# micro.net
KiCad netlist of a schematic drawn in Altium Designer
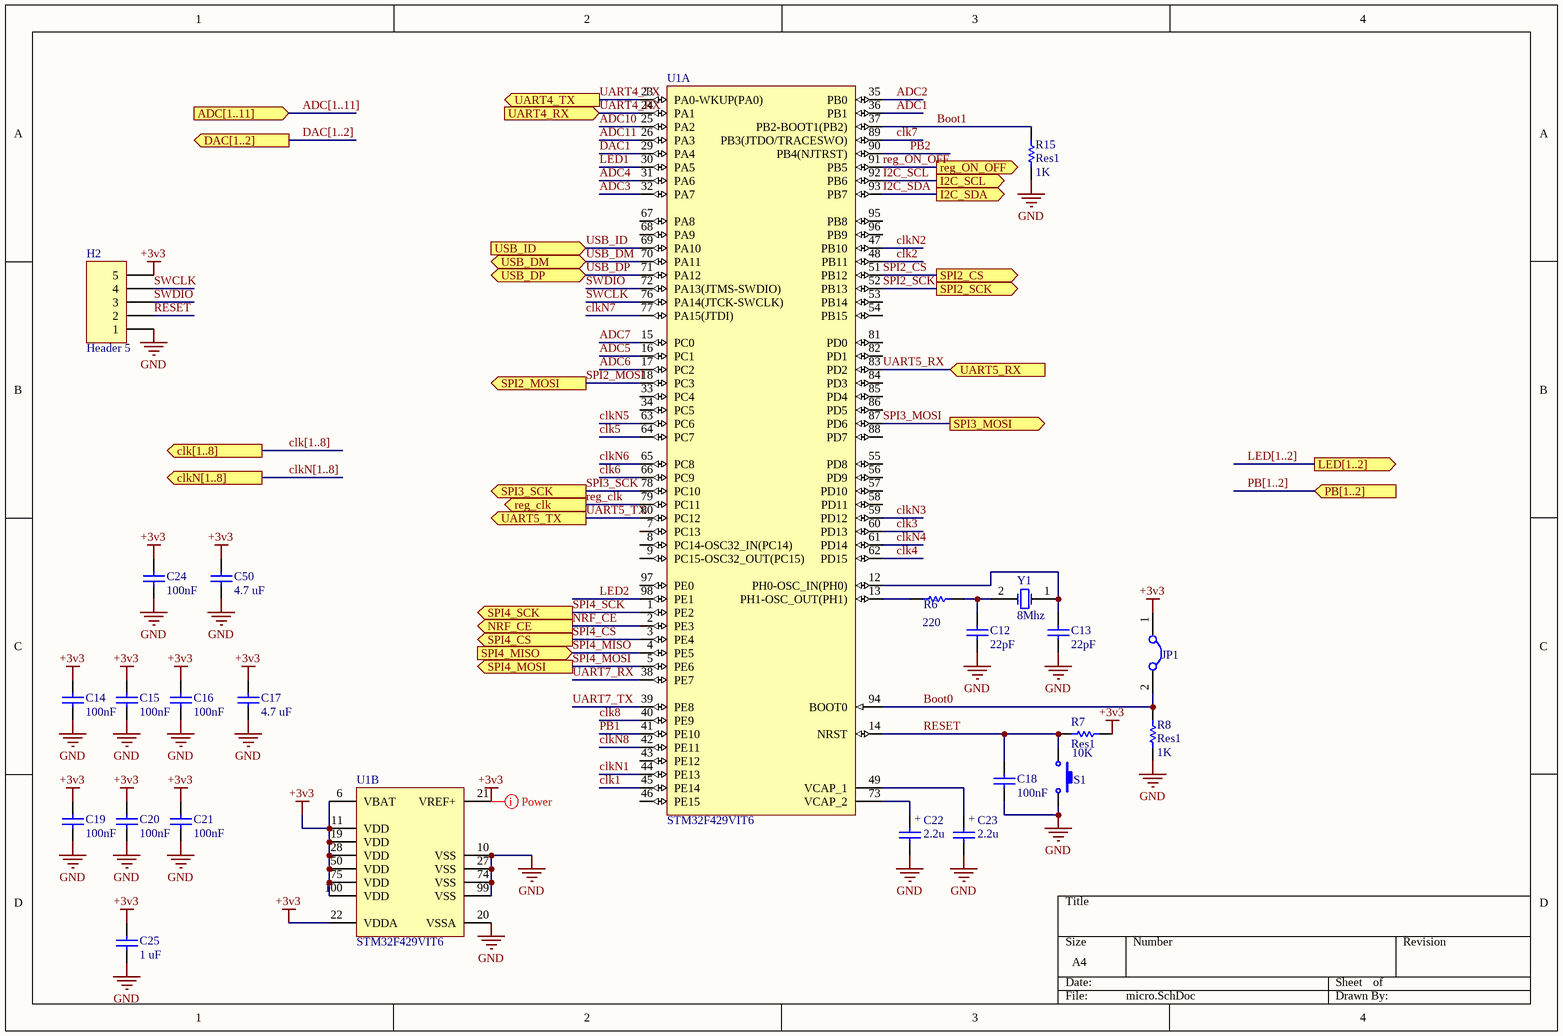
[diagram p0: micro.SchDoc]

(export (version "E")
  (design (tool "Eeschema 10.0.6"))
  (components
    (comp (ref "C12")
      (value "22pF")
      (footprint "SMD_CAP_0805")
      (description "Capacitor")
      (fields (field (name "Comment") "Cap") (field (name "PUBLISHER") "Altium Limited"))
      (libsource (lib "Miscellaneous Devices") (part "Cap"))
    )
    (comp (ref "C13")
      (value "22pF")
      (footprint "SMD_CAP_0805")
      (description "Capacitor")
      (fields (field (name "Comment") "Cap") (field (name "PUBLISHER") "Altium Limited"))
      (libsource (lib "Miscellaneous Devices") (part "Cap"))
    )
    (comp (ref "C14")
      (value "100nF")
      (footprint "SMD_CAP_0805")
      (description "Capacitor")
      (fields (field (name "PUBLISHER") "Altium Limited"))
      (libsource (lib "Miscellaneous Devices") (part "Cap"))
    )
    (comp (ref "C15")
      (value "100nF")
      (footprint "SMD_CAP_0805")
      (description "Capacitor")
      (fields (field (name "PUBLISHER") "Altium Limited"))
      (libsource (lib "Miscellaneous Devices") (part "Cap"))
    )
    (comp (ref "C16")
      (value "100nF")
      (footprint "SMD_CAP_0805")
      (description "Capacitor")
      (fields (field (name "PUBLISHER") "Altium Limited"))
      (libsource (lib "Miscellaneous Devices") (part "Cap"))
    )
    (comp (ref "C17")
      (value "4.7 uF")
      (footprint "SMD_CAP_0805")
      (fields (field (name "Comment") "Cap"))
      (libsource (lib "common0") (part "Cap"))
    )
    (comp (ref "C18")
      (value "100nF")
      (footprint "SMD_CAP_0805")
      (description "Capacitor")
      (fields (field (name "Comment") "Cap") (field (name "PUBLISHER") "Altium Limited"))
      (libsource (lib "Miscellaneous Devices") (part "Cap"))
    )
    (comp (ref "C19")
      (value "100nF")
      (footprint "SMD_CAP_0805")
      (description "Capacitor")
      (fields (field (name "PUBLISHER") "Altium Limited"))
      (libsource (lib "Miscellaneous Devices") (part "Cap"))
    )
    (comp (ref "C20")
      (value "100nF")
      (footprint "SMD_CAP_0805")
      (description "Capacitor")
      (fields (field (name "PUBLISHER") "Altium Limited"))
      (libsource (lib "Miscellaneous Devices") (part "Cap"))
    )
    (comp (ref "C21")
      (value "100nF")
      (footprint "SMD_CAP_0805")
      (description "Capacitor")
      (fields (field (name "PUBLISHER") "Altium Limited"))
      (libsource (lib "Miscellaneous Devices") (part "Cap"))
    )
    (comp (ref "C22")
      (value "2.2u")
      (footprint "CAPP 1206 (3216X18L) Size A")
      (description "tantal size a")
      (libsource (lib "Altium library (www.AVRelec.com)") (part "Cap Pol"))
    )
    (comp (ref "C23")
      (value "2.2u")
      (footprint "CAPP 1206 (3216X18L) Size A")
      (description "tantal size a")
      (libsource (lib "Altium library (www.AVRelec.com)") (part "Cap Pol"))
    )
    (comp (ref "C24")
      (value "100nF")
      (footprint "SMD_CAP_0805")
      (description "Capacitor")
      (fields (field (name "PUBLISHER") "Altium Limited"))
      (libsource (lib "Miscellaneous Devices") (part "Cap"))
    )
    (comp (ref "C25")
      (value "1 uF")
      (footprint "CAPP 1206 (3216X18L) Size A")
      (fields (field (name "Comment") "Cap"))
      (libsource (lib "common0") (part "Cap"))
    )
    (comp (ref "C50")
      (value "4.7 uF")
      (footprint "SMD_CAP_0805")
      (fields (field (name "Comment") "Cap"))
      (libsource (lib "common0") (part "Cap"))
    )
    (comp (ref "H2")
      (value "Header 5")
      (footprint "HDR1X5")
      (description "Header, 5-Pin")
      (fields (field (name "PUBLISHER") "Altium Limited"))
      (libsource (lib "Miscellaneous Connectors") (part "Header 5"))
    )
    (comp (ref "JP1")
      (value "Jumper")
      (footprint "Jumper Small - 2.54 - GRAY")
      (libsource (lib "Altium (2)") (part "Jumper"))
    )
    (comp (ref "R6")
      (value "220")
      (footprint "RES 0805 (2012X06L)")
      (description "Resistor")
      (fields (field (name "Comment") "Res1") (field (name "PUBLISHER") "Altium Limited"))
      (libsource (lib "Miscellaneous Devices") (part "Res1"))
    )
    (comp (ref "R7")
      (value "Res1")
      (footprint "RES 0805 (2012X06L)")
      (description "Resistor")
      (fields (field (name "ALTIUM_VALUE") "10K") (field (name "PUBLISHER") "Altium Limited"))
      (libsource (lib "Miscellaneous Devices") (part "Res1"))
    )
    (comp (ref "R8")
      (value "Res1")
      (footprint "RES 0805 (2012X06L)")
      (description "Resistor")
      (fields (field (name "ALTIUM_VALUE") "1K") (field (name "PUBLISHER") "Altium Limited"))
      (libsource (lib "Miscellaneous Devices") (part "Res1"))
    )
    (comp (ref "R15")
      (value "Res1")
      (footprint "RES 0805 (2012X06L)")
      (description "Resistor")
      (fields (field (name "ALTIUM_VALUE") "1K") (field (name "PUBLISHER") "Altium Limited"))
      (libsource (lib "Miscellaneous Devices") (part "Res1"))
    )
    (comp (ref "S1")
      (value "Switch PB")
      (footprint "Switch - Push to On")
      (description "Push Button Switch")
      (libsource (lib "Altium (2)") (part "Switch PB"))
    )
    (comp (ref "U1")
      (value "STM32F429VIT6")
      (footprint "STM-LQFP100_M")
      (fields (field (name "MANUFACTURER") "STMicroelectronics"))
      (libsource (lib "STMicroelectronics STM32 F4") (part "STM32F429VIT6"))
    )
    (comp (ref "Y1")
      (value "8Mhz")
      (footprint "CRYSTAL Small")
      (description "Crystal Oscillator")
      (fields (field (name "PUBLISHER") "Altium Limited"))
      (libsource (lib "Miscellaneous Devices") (part "XTAL"))
    )
  )
  (nets
    (net (code "4") (name "+3v3") (class "Default")
      (node (ref "C14") (pin "2") (pinfunction "2_2") (pintype "passive"))
      (node (ref "C15") (pin "2") (pinfunction "2_2") (pintype "passive"))
      (node (ref "C16") (pin "2") (pinfunction "2_2") (pintype "passive"))
      (node (ref "C17") (pin "1") (pinfunction "1_1") (pintype "passive"))
      (node (ref "C19") (pin "2") (pinfunction "2_2") (pintype "passive"))
      (node (ref "C20") (pin "2") (pinfunction "2_2") (pintype "passive"))
      (node (ref "C21") (pin "2") (pinfunction "2_2") (pintype "passive"))
      (node (ref "C24") (pin "2") (pinfunction "2_2") (pintype "passive"))
      (node (ref "C25") (pin "1") (pinfunction "1_1") (pintype "passive"))
      (node (ref "C50") (pin "1") (pinfunction "1_1") (pintype "passive"))
      (node (ref "H2") (pin "5") (pinfunction "5_5") (pintype "passive"))
      (node (ref "JP1") (pin "1") (pinfunction "1_1") (pintype "passive"))
      (node (ref "R7") (pin "1") (pinfunction "1_1") (pintype "passive"))
      (node (ref "U1") (pin "100") (pinfunction "VDD_100") (pintype "power_in"))
      (node (ref "U1") (pin "11") (pinfunction "VDD_11") (pintype "power_in"))
      (node (ref "U1") (pin "19") (pinfunction "VDD_19") (pintype "power_in"))
      (node (ref "U1") (pin "21") (pinfunction "VREF+_21") (pintype "power_in"))
      (node (ref "U1") (pin "22") (pinfunction "VDDA_22") (pintype "power_in"))
      (node (ref "U1") (pin "28") (pinfunction "VDD_28") (pintype "power_in"))
      (node (ref "U1") (pin "50") (pinfunction "VDD_50") (pintype "power_in"))
      (node (ref "U1") (pin "6") (pinfunction "VBAT_6") (pintype "power_in"))
      (node (ref "U1") (pin "75") (pinfunction "VDD_75") (pintype "power_in"))
    )
    (net (code "5") (name "/ADC1") (class "Default")
      (node (ref "U1") (pin "36") (pinfunction "PB1_36") (pintype "bidirectional"))
    )
    (net (code "6") (name "/ADC2") (class "Default")
      (node (ref "U1") (pin "35") (pinfunction "PB0_35") (pintype "bidirectional"))
    )
    (net (code "7") (name "/ADC3") (class "Default")
      (node (ref "U1") (pin "32") (pinfunction "PA7_32") (pintype "bidirectional"))
    )
    (net (code "8") (name "/ADC4") (class "Default")
      (node (ref "U1") (pin "31") (pinfunction "PA6_31") (pintype "bidirectional"))
    )
    (net (code "9") (name "/ADC5") (class "Default")
      (node (ref "U1") (pin "16") (pinfunction "PC1_16") (pintype "bidirectional"))
    )
    (net (code "10") (name "/ADC6") (class "Default")
      (node (ref "U1") (pin "17") (pinfunction "PC2_17") (pintype "bidirectional"))
    )
    (net (code "11") (name "/ADC7") (class "Default")
      (node (ref "U1") (pin "15") (pinfunction "PC0_15") (pintype "bidirectional"))
    )
    (net (code "12") (name "/ADC10") (class "Default")
      (node (ref "U1") (pin "25") (pinfunction "PA2_25") (pintype "bidirectional"))
    )
    (net (code "13") (name "/ADC11") (class "Default")
      (node (ref "U1") (pin "26") (pinfunction "PA3_26") (pintype "bidirectional"))
    )
    (net (code "15") (name "/Boot0") (class "Default")
      (node (ref "JP1") (pin "2") (pinfunction "2_2") (pintype "passive"))
      (node (ref "R8") (pin "2") (pinfunction "2_2") (pintype "passive"))
      (node (ref "U1") (pin "94") (pinfunction "BOOT0_94") (pintype "input"))
    )
    (net (code "16") (name "/Boot1") (class "Default")
      (node (ref "R15") (pin "2") (pinfunction "2_2") (pintype "passive"))
      (node (ref "U1") (pin "37") (pinfunction "PB2-BOOT1(PB2)_37") (pintype "bidirectional"))
    )
    (net (code "17") (name "/DAC1") (class "Default")
      (node (ref "U1") (pin "29") (pinfunction "PA4_29") (pintype "bidirectional"))
    )
    (net (code "19") (name "/I2C_SCL") (class "Default")
      (node (ref "U1") (pin "92") (pinfunction "PB6_92") (pintype "bidirectional"))
    )
    (net (code "20") (name "/I2C_SDA") (class "Default")
      (node (ref "U1") (pin "93") (pinfunction "PB7_93") (pintype "bidirectional"))
    )
    (net (code "21") (name "/LED1") (class "Default")
      (node (ref "U1") (pin "30") (pinfunction "PA5_30") (pintype "bidirectional"))
    )
    (net (code "22") (name "/LED2") (class "Default")
      (node (ref "U1") (pin "98") (pinfunction "PE1_98") (pintype "bidirectional"))
    )
    (net (code "24") (name "/NRF_CE") (class "Default")
      (node (ref "U1") (pin "2") (pinfunction "PE3_2") (pintype "bidirectional"))
    )
    (net (code "25") (name "/PB1") (class "Default")
      (node (ref "U1") (pin "41") (pinfunction "PE10_41") (pintype "bidirectional"))
    )
    (net (code "26") (name "/PB2") (class "Default")
      (node (ref "U1") (pin "90") (pinfunction "PB4(NJTRST)_90") (pintype "bidirectional"))
    )
    (net (code "28") (name "/RESET") (class "Default")
      (node (ref "C18") (pin "2") (pinfunction "2_2") (pintype "passive"))
      (node (ref "H2") (pin "2") (pinfunction "2_2") (pintype "passive"))
      (node (ref "R7") (pin "2") (pinfunction "2_2") (pintype "passive"))
      (node (ref "S1") (pin "1") (pinfunction "1_1") (pintype "passive"))
      (node (ref "U1") (pin "14") (pinfunction "NRST_14") (pintype "bidirectional"))
    )
    (net (code "29") (name "/SPI2_CS") (class "Default")
      (node (ref "U1") (pin "51") (pinfunction "PB12_51") (pintype "bidirectional"))
    )
    (net (code "30") (name "/SPI2_MOSI") (class "Default")
      (node (ref "U1") (pin "18") (pinfunction "PC3_18") (pintype "bidirectional"))
    )
    (net (code "31") (name "/SPI2_SCK") (class "Default")
      (node (ref "U1") (pin "52") (pinfunction "PB13_52") (pintype "bidirectional"))
    )
    (net (code "32") (name "/SPI3_MOSI") (class "Default")
      (node (ref "U1") (pin "87") (pinfunction "PD6_87") (pintype "bidirectional"))
    )
    (net (code "33") (name "/SPI3_SCK") (class "Default")
      (node (ref "U1") (pin "78") (pinfunction "PC10_78") (pintype "bidirectional"))
    )
    (net (code "34") (name "/SPI4_CS") (class "Default")
      (node (ref "U1") (pin "3") (pinfunction "PE4_3") (pintype "bidirectional"))
    )
    (net (code "35") (name "/SPI4_MISO") (class "Default")
      (node (ref "U1") (pin "4") (pinfunction "PE5_4") (pintype "bidirectional"))
    )
    (net (code "36") (name "/SPI4_MOSI") (class "Default")
      (node (ref "U1") (pin "5") (pinfunction "PE6_5") (pintype "bidirectional"))
    )
    (net (code "37") (name "/SPI4_SCK") (class "Default")
      (node (ref "U1") (pin "1") (pinfunction "PE2_1") (pintype "bidirectional"))
    )
    (net (code "38") (name "/SWCLK") (class "Default")
      (node (ref "H2") (pin "4") (pinfunction "4_4") (pintype "passive"))
      (node (ref "U1") (pin "76") (pinfunction "PA14(JTCK-SWCLK)_76") (pintype "bidirectional"))
    )
    (net (code "39") (name "/SWDIO") (class "Default")
      (node (ref "H2") (pin "3") (pinfunction "3_3") (pintype "passive"))
      (node (ref "U1") (pin "72") (pinfunction "PA13(JTMS-SWDIO)_72") (pintype "bidirectional"))
    )
    (net (code "40") (name "/UART4_RX") (class "Default")
      (node (ref "U1") (pin "24") (pinfunction "PA1_24") (pintype "bidirectional"))
    )
    (net (code "41") (name "/UART4_TX") (class "Default")
      (node (ref "U1") (pin "23") (pinfunction "PA0-WKUP(PA0)_23") (pintype "bidirectional"))
    )
    (net (code "42") (name "/UART5_RX") (class "Default")
      (node (ref "U1") (pin "83") (pinfunction "PD2_83") (pintype "bidirectional"))
    )
    (net (code "43") (name "/UART5_TX") (class "Default")
      (node (ref "U1") (pin "80") (pinfunction "PC12_80") (pintype "bidirectional"))
    )
    (net (code "44") (name "/UART7_RX") (class "Default")
      (node (ref "U1") (pin "38") (pinfunction "PE7_38") (pintype "bidirectional"))
    )
    (net (code "45") (name "/UART7_TX") (class "Default")
      (node (ref "U1") (pin "39") (pinfunction "PE8_39") (pintype "bidirectional"))
    )
    (net (code "46") (name "/USB_DM") (class "Default")
      (node (ref "U1") (pin "70") (pinfunction "PA11_70") (pintype "bidirectional"))
    )
    (net (code "47") (name "/USB_DP") (class "Default")
      (node (ref "U1") (pin "71") (pinfunction "PA12_71") (pintype "bidirectional"))
    )
    (net (code "48") (name "/USB_ID") (class "Default")
      (node (ref "U1") (pin "69") (pinfunction "PA10_69") (pintype "bidirectional"))
    )
    (net (code "49") (name "/clk1") (class "Default")
      (node (ref "U1") (pin "45") (pinfunction "PE14_45") (pintype "bidirectional"))
    )
    (net (code "50") (name "/clk2") (class "Default")
      (node (ref "U1") (pin "48") (pinfunction "PB11_48") (pintype "bidirectional"))
    )
    (net (code "51") (name "/clk3") (class "Default")
      (node (ref "U1") (pin "60") (pinfunction "PD13_60") (pintype "bidirectional"))
    )
    (net (code "52") (name "/clk4") (class "Default")
      (node (ref "U1") (pin "62") (pinfunction "PD15_62") (pintype "bidirectional"))
    )
    (net (code "53") (name "/clk5") (class "Default")
      (node (ref "U1") (pin "64") (pinfunction "PC7_64") (pintype "bidirectional"))
    )
    (net (code "54") (name "/clk6") (class "Default")
      (node (ref "U1") (pin "66") (pinfunction "PC9_66") (pintype "bidirectional"))
    )
    (net (code "55") (name "/clk7") (class "Default")
      (node (ref "U1") (pin "89") (pinfunction "PB3(JTDO/TRACESWO)_89") (pintype "bidirectional"))
    )
    (net (code "56") (name "/clk8") (class "Default")
      (node (ref "U1") (pin "40") (pinfunction "PE9_40") (pintype "bidirectional"))
    )
    (net (code "57") (name "/clkN1") (class "Default")
      (node (ref "U1") (pin "44") (pinfunction "PE13_44") (pintype "bidirectional"))
    )
    (net (code "58") (name "/clkN2") (class "Default")
      (node (ref "U1") (pin "47") (pinfunction "PB10_47") (pintype "bidirectional"))
    )
    (net (code "59") (name "/clkN3") (class "Default")
      (node (ref "U1") (pin "59") (pinfunction "PD12_59") (pintype "bidirectional"))
    )
    (net (code "60") (name "/clkN4") (class "Default")
      (node (ref "U1") (pin "61") (pinfunction "PD14_61") (pintype "bidirectional"))
    )
    (net (code "61") (name "/clkN5") (class "Default")
      (node (ref "U1") (pin "63") (pinfunction "PC6_63") (pintype "bidirectional"))
    )
    (net (code "62") (name "/clkN6") (class "Default")
      (node (ref "U1") (pin "65") (pinfunction "PC8_65") (pintype "bidirectional"))
    )
    (net (code "63") (name "/clkN7") (class "Default")
      (node (ref "U1") (pin "77") (pinfunction "PA15(JTDI)_77") (pintype "bidirectional"))
    )
    (net (code "64") (name "/clkN8") (class "Default")
      (node (ref "U1") (pin "42") (pinfunction "PE11_42") (pintype "bidirectional"))
    )
    (net (code "67") (name "/reg_ON_OFF") (class "Default")
      (node (ref "U1") (pin "91") (pinfunction "PB5_91") (pintype "bidirectional"))
    )
    (net (code "68") (name "/reg_clk") (class "Default")
      (node (ref "U1") (pin "79") (pinfunction "PC11_79") (pintype "bidirectional"))
    )
    (net (code "69") (name "GND") (class "Default")
      (node (ref "C12") (pin "1") (pinfunction "1_1") (pintype "passive"))
      (node (ref "C13") (pin "1") (pinfunction "1_1") (pintype "passive"))
      (node (ref "C14") (pin "1") (pinfunction "1_1") (pintype "passive"))
      (node (ref "C15") (pin "1") (pinfunction "1_1") (pintype "passive"))
      (node (ref "C16") (pin "1") (pinfunction "1_1") (pintype "passive"))
      (node (ref "C17") (pin "2") (pinfunction "2_2") (pintype "passive"))
      (node (ref "C18") (pin "1") (pinfunction "1_1") (pintype "passive"))
      (node (ref "C19") (pin "1") (pinfunction "1_1") (pintype "passive"))
      (node (ref "C20") (pin "1") (pinfunction "1_1") (pintype "passive"))
      (node (ref "C21") (pin "1") (pinfunction "1_1") (pintype "passive"))
      (node (ref "C22") (pin "-") (pinfunction "-_-") (pintype "passive"))
      (node (ref "C23") (pin "-") (pinfunction "-_-") (pintype "passive"))
      (node (ref "C24") (pin "1") (pinfunction "1_1") (pintype "passive"))
      (node (ref "C25") (pin "2") (pinfunction "2_2") (pintype "passive"))
      (node (ref "C50") (pin "2") (pinfunction "2_2") (pintype "passive"))
      (node (ref "H2") (pin "1") (pinfunction "1_1") (pintype "passive"))
      (node (ref "R15") (pin "1") (pinfunction "1_1") (pintype "passive"))
      (node (ref "R8") (pin "1") (pinfunction "1_1") (pintype "passive"))
      (node (ref "S1") (pin "2") (pinfunction "2_2") (pintype "passive"))
      (node (ref "U1") (pin "10") (pinfunction "VSS_10") (pintype "power_in"))
      (node (ref "U1") (pin "20") (pinfunction "VSSA_20") (pintype "power_in"))
      (node (ref "U1") (pin "27") (pinfunction "VSS_27") (pintype "power_in"))
      (node (ref "U1") (pin "74") (pinfunction "VSS_74") (pintype "power_in"))
      (node (ref "U1") (pin "99") (pinfunction "VSS_99") (pintype "power_in"))
    )
    (net (code "70") (name "Net-(U1A-PH0-OSC_IN(PH0))") (class "Default")
      (node (ref "C13") (pin "2") (pinfunction "2_2") (pintype "passive"))
      (node (ref "U1") (pin "12") (pinfunction "PH0-OSC_IN(PH0)_12") (pintype "bidirectional"))
      (node (ref "Y1") (pin "1") (pinfunction "OSC1_1") (pintype "passive"))
    )
    (net (code "71") (name "Net-(U1A-PH1-OSC_OUT(PH1))") (class "Default")
      (node (ref "R6") (pin "1") (pinfunction "1_1") (pintype "passive"))
      (node (ref "U1") (pin "13") (pinfunction "PH1-OSC_OUT(PH1)_13") (pintype "bidirectional"))
    )
    (net (code "72") (name "Net-(U1A-VCAP_1)") (class "Default")
      (node (ref "C23") (pin "+") (pinfunction "+_+") (pintype "passive"))
      (node (ref "U1") (pin "49") (pinfunction "VCAP_1_49") (pintype "power_in"))
    )
    (net (code "73") (name "Net-(U1A-VCAP_2)") (class "Default")
      (node (ref "C22") (pin "+") (pinfunction "+_+") (pintype "passive"))
      (node (ref "U1") (pin "73") (pinfunction "VCAP_2_73") (pintype "power_in"))
    )
    (net (code "74") (name "Net-(Y1-OSC2)") (class "Default")
      (node (ref "C12") (pin "2") (pinfunction "2_2") (pintype "passive"))
      (node (ref "R6") (pin "2") (pinfunction "2_2") (pintype "passive"))
      (node (ref "Y1") (pin "2") (pinfunction "OSC2_2") (pintype "passive"))
    )
    (net (code "75") (name "unconnected-(U1A-PA8-Pad67)") (class "Default")
      (node (ref "U1") (pin "67") (pinfunction "PA8_67") (pintype "bidirectional"))
    )
    (net (code "76") (name "unconnected-(U1A-PA9-Pad68)") (class "Default")
      (node (ref "U1") (pin "68") (pinfunction "PA9_68") (pintype "bidirectional"))
    )
    (net (code "77") (name "unconnected-(U1A-PB8-Pad95)") (class "Default")
      (node (ref "U1") (pin "95") (pinfunction "PB8_95") (pintype "bidirectional"))
    )
    (net (code "78") (name "unconnected-(U1A-PB9-Pad96)") (class "Default")
      (node (ref "U1") (pin "96") (pinfunction "PB9_96") (pintype "bidirectional"))
    )
    (net (code "79") (name "unconnected-(U1A-PB14-Pad53)") (class "Default")
      (node (ref "U1") (pin "53") (pinfunction "PB14_53") (pintype "bidirectional"))
    )
    (net (code "80") (name "unconnected-(U1A-PB15-Pad54)") (class "Default")
      (node (ref "U1") (pin "54") (pinfunction "PB15_54") (pintype "bidirectional"))
    )
    (net (code "81") (name "unconnected-(U1A-PC4-Pad33)") (class "Default")
      (node (ref "U1") (pin "33") (pinfunction "PC4_33") (pintype "bidirectional"))
    )
    (net (code "82") (name "unconnected-(U1A-PC5-Pad34)") (class "Default")
      (node (ref "U1") (pin "34") (pinfunction "PC5_34") (pintype "bidirectional"))
    )
    (net (code "83") (name "unconnected-(U1A-PC13-Pad7)") (class "Default")
      (node (ref "U1") (pin "7") (pinfunction "PC13_7") (pintype "bidirectional"))
    )
    (net (code "84") (name "unconnected-(U1A-PC14-OSC32_IN(PC14)-Pad8)") (class "Default")
      (node (ref "U1") (pin "8") (pinfunction "PC14-OSC32_IN(PC14)_8") (pintype "bidirectional"))
    )
    (net (code "85") (name "unconnected-(U1A-PC15-OSC32_OUT(PC15)-Pad9)") (class "Default")
      (node (ref "U1") (pin "9") (pinfunction "PC15-OSC32_OUT(PC15)_9") (pintype "bidirectional"))
    )
    (net (code "86") (name "unconnected-(U1A-PD0-Pad81)") (class "Default")
      (node (ref "U1") (pin "81") (pinfunction "PD0_81") (pintype "bidirectional"))
    )
    (net (code "87") (name "unconnected-(U1A-PD1-Pad82)") (class "Default")
      (node (ref "U1") (pin "82") (pinfunction "PD1_82") (pintype "bidirectional"))
    )
    (net (code "88") (name "unconnected-(U1A-PD3-Pad84)") (class "Default")
      (node (ref "U1") (pin "84") (pinfunction "PD3_84") (pintype "bidirectional"))
    )
    (net (code "89") (name "unconnected-(U1A-PD4-Pad85)") (class "Default")
      (node (ref "U1") (pin "85") (pinfunction "PD4_85") (pintype "bidirectional"))
    )
    (net (code "90") (name "unconnected-(U1A-PD5-Pad86)") (class "Default")
      (node (ref "U1") (pin "86") (pinfunction "PD5_86") (pintype "bidirectional"))
    )
    (net (code "91") (name "unconnected-(U1A-PD7-Pad88)") (class "Default")
      (node (ref "U1") (pin "88") (pinfunction "PD7_88") (pintype "bidirectional"))
    )
    (net (code "92") (name "unconnected-(U1A-PD8-Pad55)") (class "Default")
      (node (ref "U1") (pin "55") (pinfunction "PD8_55") (pintype "bidirectional"))
    )
    (net (code "93") (name "unconnected-(U1A-PD9-Pad56)") (class "Default")
      (node (ref "U1") (pin "56") (pinfunction "PD9_56") (pintype "bidirectional"))
    )
    (net (code "94") (name "unconnected-(U1A-PD10-Pad57)") (class "Default")
      (node (ref "U1") (pin "57") (pinfunction "PD10_57") (pintype "bidirectional"))
    )
    (net (code "95") (name "unconnected-(U1A-PD11-Pad58)") (class "Default")
      (node (ref "U1") (pin "58") (pinfunction "PD11_58") (pintype "bidirectional"))
    )
    (net (code "96") (name "unconnected-(U1A-PE0-Pad97)") (class "Default")
      (node (ref "U1") (pin "97") (pinfunction "PE0_97") (pintype "bidirectional"))
    )
    (net (code "97") (name "unconnected-(U1A-PE12-Pad43)") (class "Default")
      (node (ref "U1") (pin "43") (pinfunction "PE12_43") (pintype "bidirectional"))
    )
    (net (code "98") (name "unconnected-(U1A-PE15-Pad46)") (class "Default")
      (node (ref "U1") (pin "46") (pinfunction "PE15_46") (pintype "bidirectional"))
    )
  )
)
